# Power.net
KiCad netlist of a schematic drawn in Altium Designer
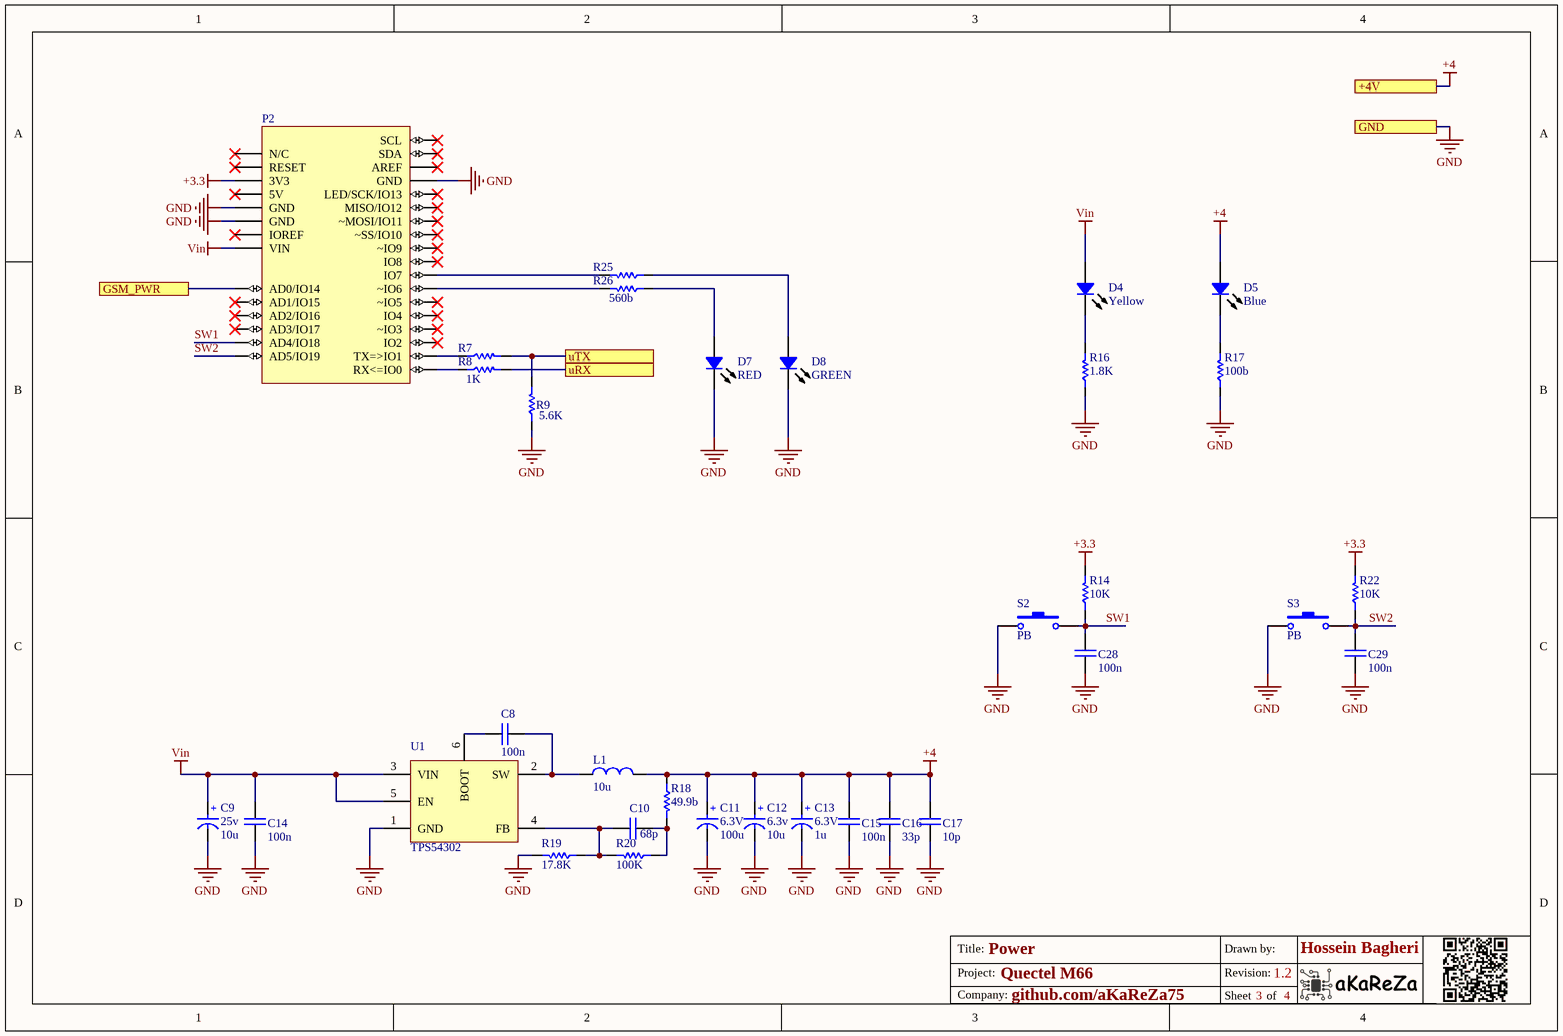
[diagram p0: Power.SchDoc]

(export (version "E")
  (design (tool "Eeschema 10.0.6"))
  (components
    (comp (ref "C8")
      (value "100n")
      (footprint "CAP 0805/2012")
      (description "Bipolar ceramic capacitor SMD")
      (fields (field (name "VALIDATION") "Valid"))
      (libsource (lib "aKaReZa") (part "Cap_Multi_SMD_100nF_0805"))
    )
    (comp (ref "C9")
      (value "10u")
      (footprint "SMT_C_Tantalum_B")
      (description "Tantalum Capacitor,TAJ Series-SMD")
      (fields (field (name "RATING") "25v") (field (name "VALIDATION") "Valid"))
      (libsource (lib "aKaReZa") (part "Cap_Tantalum"))
    )
    (comp (ref "C10")
      (value "68p")
      (footprint "CAP 0805/2012")
      (description "Bipolar ceramic capacitor SMD")
      (fields (field (name "VALIDATION") "Valid"))
      (libsource (lib "aKaReZa") (part "Cap_Multi_SMD_0805"))
    )
    (comp (ref "C11")
      (value "100u")
      (footprint "SMT_C_Tantalum_C")
      (description "Tantalum Capacitor,TAJ Series-SMD")
      (fields (field (name "RATING") "6.3V"))
      (libsource (lib "aKaReZa") (part "Cap_Tantalum"))
    )
    (comp (ref "C12")
      (value "10u")
      (footprint "SMT_C_Tantalum_A")
      (description "Tantalum Capacitor,TAJ Series-SMD")
      (fields (field (name "RATING") "6.3v") (field (name "VALIDATION") "Valid"))
      (libsource (lib "aKaReZa") (part "Cap_Tantalum"))
    )
    (comp (ref "C13")
      (value "1u")
      (footprint "SMT_C_Tantalum_A")
      (description "Tantalum Capacitor,TAJ Series-SMD")
      (fields (field (name "RATING") "6.3V"))
      (libsource (lib "aKaReZa") (part "Cap_Tantalum"))
    )
    (comp (ref "C14")
      (value "100n")
      (footprint "CAP 1206/3216")
      (description "Bipolar ceramic capacitor SMD")
      (fields (field (name "VALIDATION") "Valid"))
      (libsource (lib "aKaReZa") (part "Cap_Multi_SMD_100nF_1206"))
    )
    (comp (ref "C15")
      (value "100n")
      (footprint "CAP 1206/3216")
      (description "Bipolar ceramic capacitor SMD")
      (libsource (lib "aKaReZa") (part "Cap_Multi_SMD_100nF_1206"))
    )
    (comp (ref "C16")
      (value "33p")
      (footprint "CAP 1206/3216")
      (description "Bipolar ceramic capacitor SMD")
      (libsource (lib "aKaReZa") (part "Cap_Multi_SMD_1206"))
    )
    (comp (ref "C17")
      (value "10p")
      (footprint "CAP 1206/3216")
      (description "Bipolar ceramic capacitor SMD")
      (libsource (lib "aKaReZa") (part "Cap_Multi_SMD_1206"))
    )
    (comp (ref "C28")
      (value "100n")
      (footprint "CAP 0805/2012")
      (description "Bipolar ceramic capacitor SMD")
      (fields (field (name "VALIDATION") "Valid"))
      (libsource (lib "aKaReZa") (part "Cap_Multi_SMD_100nF_0805"))
    )
    (comp (ref "C29")
      (value "100n")
      (footprint "CAP 0805/2012")
      (description "Bipolar ceramic capacitor SMD")
      (fields (field (name "VALIDATION") "Valid"))
      (libsource (lib "aKaReZa") (part "Cap_Multi_SMD_100nF_0805"))
    )
    (comp (ref "D4")
      (value "Yellow")
      (footprint "LED 0805/2012 YELLOW")
      (description "LED")
      (fields (field (name "VALIDATION") "Valid"))
      (libsource (lib "aKaReZa") (part "Semi_LED_SMD"))
    )
    (comp (ref "D5")
      (value "Blue")
      (footprint "LED 0805/2012 BLUE")
      (description "LED")
      (fields (field (name "VALIDATION") "Valid"))
      (libsource (lib "aKaReZa") (part "Semi_LED_SMD"))
    )
    (comp (ref "D7")
      (value "RED")
      (footprint "LED 0805/2012 RED")
      (description "LED")
      (fields (field (name "VALIDATION") "Valid"))
      (libsource (lib "aKaReZa") (part "Semi_LED_SMD"))
    )
    (comp (ref "D8")
      (value "GREEN")
      (footprint "LED 0805/2012 GREEN")
      (description "LED")
      (fields (field (name "VALIDATION") "Valid"))
      (libsource (lib "aKaReZa") (part "Semi_LED_SMD"))
    )
    (comp (ref "L1")
      (value "10u")
      (footprint "L_7")
      (description "Inductor")
      (fields (field (name "VALIDATION") "Valid"))
      (libsource (lib "aKaReZa") (part "Ind_SMD"))
    )
    (comp (ref "P2")
      (value "UNO")
      (footprint "Arduino_uno_S_3")
      (description "Arduino uno slave")
      (fields (field (name "VALIDATION") "Valid"))
      (libsource (lib "aKaReZa") (part "Con_Arduino_UNO_S"))
    )
    (comp (ref "R7")
      (value "1K")
      (footprint "RES 0805 (2012X06L)")
      (description "Resistor")
      (fields (field (name "VALIDATION") "Valid"))
      (libsource (lib "aKaReZa") (part "Res_SMD_0805"))
    )
    (comp (ref "R8")
      (value "1K")
      (footprint "RES 0805 (2012X06L)")
      (description "Resistor")
      (fields (field (name "VALIDATION") "Valid"))
      (libsource (lib "aKaReZa") (part "Res_SMD_0805"))
    )
    (comp (ref "R9")
      (value "5.6K")
      (footprint "RES 0805 (2012X06L)")
      (description "Resistor")
      (fields (field (name "VALIDATION") "Valid"))
      (libsource (lib "aKaReZa") (part "Res_SMD_0805"))
    )
    (comp (ref "R14")
      (value "10K")
      (footprint "RES 0805 (2012X06L)")
      (description "Resistor")
      (fields (field (name "VALIDATION") "Valid"))
      (libsource (lib "aKaReZa") (part "Res_SMD_0805"))
    )
    (comp (ref "R16")
      (value "1.8K")
      (footprint "RES 0805 (2012X06L)")
      (description "Resistor")
      (fields (field (name "VALIDATION") "Valid"))
      (libsource (lib "aKaReZa") (part "Res_SMD_0805"))
    )
    (comp (ref "R17")
      (value "100b")
      (footprint "RES 0805 (2012X06L)")
      (description "Resistor")
      (fields (field (name "VALIDATION") "Valid"))
      (libsource (lib "aKaReZa") (part "Res_SMD_0805"))
    )
    (comp (ref "R18")
      (value "49.9b")
      (footprint "RES 0805 (2012X06L)")
      (description "Resistor")
      (fields (field (name "VALIDATION") "Valid"))
      (libsource (lib "aKaReZa") (part "Res_SMD_0805"))
    )
    (comp (ref "R19")
      (value "17.8K")
      (footprint "RES 0805 (2012X06L)")
      (description "Resistor")
      (fields (field (name "VALIDATION") "Valid"))
      (libsource (lib "aKaReZa") (part "Res_SMD_0805"))
    )
    (comp (ref "R20")
      (value "100K")
      (footprint "RES 0805 (2012X06L)")
      (description "Resistor")
      (fields (field (name "VALIDATION") "Valid"))
      (libsource (lib "aKaReZa") (part "Res_SMD_0805"))
    )
    (comp (ref "R22")
      (value "10K")
      (footprint "RES 0805 (2012X06L)")
      (description "Resistor")
      (fields (field (name "VALIDATION") "Valid"))
      (libsource (lib "aKaReZa") (part "Res_SMD_0805"))
    )
    (comp (ref "R25")
      (value "560b")
      (footprint "RES 0805 (2012X06L)")
      (description "Resistor")
      (fields (field (name "VALIDATION") "Valid"))
      (libsource (lib "aKaReZa") (part "Res_SMD_0805"))
    )
    (comp (ref "R26")
      (value "560b")
      (footprint "RES 0805 (2012X06L)")
      (description "Resistor")
      (fields (field (name "VALIDATION") "Valid"))
      (libsource (lib "aKaReZa") (part "Res_SMD_0805"))
    )
    (comp (ref "S2")
      (value "PB")
      (footprint "SW_PB_SMD_2PIN_SPST_6X3X2")
      (description "SMT Tactile ‎Switch")
      (fields (field (name "VALIDATION") "Valid"))
      (libsource (lib "aKaReZa") (part "SW_PushButton_2_SMD"))
    )
    (comp (ref "S3")
      (value "PB")
      (footprint "SW_PB_SMD_2PIN_SPST_6X3X2")
      (description "SMT Tactile ‎Switch")
      (fields (field (name "VALIDATION") "Valid"))
      (libsource (lib "aKaReZa") (part "SW_PushButton_2_SMD"))
    )
    (comp (ref "U1")
      (value "TPS54302")
      (footprint "TPS54302")
      (description "3'A Synchronous Step-Down Converter")
      (fields (field (name "VALIDATION") "Valid"))
      (libsource (lib "aKaReZa") (part "IC_Reg_TPS54302"))
    )
  )
  (nets
    (net (code "1") (name "+3.3") (class "Default")
      (node (ref "P2") (pin "4") (pinfunction "3V3_4") (pintype "power_in"))
      (node (ref "R14") (pin "2") (pinfunction "2_2") (pintype "passive"))
      (node (ref "R22") (pin "2") (pinfunction "2_2") (pintype "passive"))
    )
    (net (code "2") (name "+4") (class "Default")
      (node (ref "C11") (pin "1") (pinfunction "+_1") (pintype "passive"))
      (node (ref "C12") (pin "1") (pinfunction "+_1") (pintype "passive"))
      (node (ref "C13") (pin "1") (pinfunction "+_1") (pintype "passive"))
      (node (ref "C15") (pin "1") (pinfunction "1_1") (pintype "passive"))
      (node (ref "C16") (pin "1") (pinfunction "1_1") (pintype "passive"))
      (node (ref "C17") (pin "1") (pinfunction "1_1") (pintype "passive"))
      (node (ref "D5") (pin "1") (pinfunction "1_1") (pintype "passive"))
      (node (ref "L1") (pin "2") (pinfunction "2_2") (pintype "passive"))
      (node (ref "R18") (pin "1") (pinfunction "1_1") (pintype "passive"))
    )
    (net (code "3") (name "/GSM_PWR") (class "Default")
      (node (ref "P2") (pin "9") (pinfunction "AD0/IO14_9") (pintype "bidirectional"))
    )
    (net (code "4") (name "/SW1") (class "Default")
      (node (ref "C28") (pin "1") (pinfunction "1_1") (pintype "passive"))
      (node (ref "P2") (pin "13") (pinfunction "AD4/IO18_13") (pintype "bidirectional"))
      (node (ref "R14") (pin "1") (pinfunction "1_1") (pintype "passive"))
      (node (ref "S2") (pin "1") (pinfunction "1_1") (pintype "passive"))
    )
    (net (code "5") (name "/SW2") (class "Default")
      (node (ref "C29") (pin "1") (pinfunction "1_1") (pintype "passive"))
      (node (ref "P2") (pin "14") (pinfunction "AD5/IO19_14") (pintype "bidirectional"))
      (node (ref "R22") (pin "1") (pinfunction "1_1") (pintype "passive"))
      (node (ref "S3") (pin "1") (pinfunction "1_1") (pintype "passive"))
    )
    (net (code "6") (name "/uRX") (class "Default")
      (node (ref "R8") (pin "2") (pinfunction "2_2") (pintype "passive"))
    )
    (net (code "7") (name "/uTX") (class "Default")
      (node (ref "R7") (pin "2") (pinfunction "2_2") (pintype "passive"))
      (node (ref "R9") (pin "2") (pinfunction "2_2") (pintype "passive"))
    )
    (net (code "8") (name "GND") (class "Default")
      (node (ref "C11") (pin "2") (pinfunction "-_2") (pintype "passive"))
      (node (ref "C12") (pin "2") (pinfunction "-_2") (pintype "passive"))
      (node (ref "C13") (pin "2") (pinfunction "-_2") (pintype "passive"))
      (node (ref "C14") (pin "2") (pinfunction "2_2") (pintype "passive"))
      (node (ref "C15") (pin "2") (pinfunction "2_2") (pintype "passive"))
      (node (ref "C16") (pin "2") (pinfunction "2_2") (pintype "passive"))
      (node (ref "C17") (pin "2") (pinfunction "2_2") (pintype "passive"))
      (node (ref "C28") (pin "2") (pinfunction "2_2") (pintype "passive"))
      (node (ref "C29") (pin "2") (pinfunction "2_2") (pintype "passive"))
      (node (ref "C9") (pin "2") (pinfunction "-_2") (pintype "passive"))
      (node (ref "D7") (pin "2") (pinfunction "2_2") (pintype "passive"))
      (node (ref "D8") (pin "2") (pinfunction "2_2") (pintype "passive"))
      (node (ref "P2") (pin "29") (pinfunction "GND_29") (pintype "power_in"))
      (node (ref "P2") (pin "6") (pinfunction "GND_6") (pintype "power_in"))
      (node (ref "P2") (pin "7") (pinfunction "GND_7") (pintype "power_in"))
      (node (ref "R16") (pin "1") (pinfunction "1_1") (pintype "passive"))
      (node (ref "R17") (pin "1") (pinfunction "1_1") (pintype "passive"))
      (node (ref "R19") (pin "2") (pinfunction "2_2") (pintype "passive"))
      (node (ref "R9") (pin "1") (pinfunction "1_1") (pintype "passive"))
      (node (ref "S2") (pin "2") (pinfunction "2_2") (pintype "passive"))
      (node (ref "S3") (pin "2") (pinfunction "2_2") (pintype "passive"))
      (node (ref "U1") (pin "1") (pinfunction "GND_1") (pintype "power_in"))
    )
    (net (code "9") (name "Net-(C10-Pad2)") (class "Default")
      (node (ref "C10") (pin "2") (pinfunction "2_2") (pintype "passive"))
      (node (ref "R18") (pin "2") (pinfunction "2_2") (pintype "passive"))
      (node (ref "R20") (pin "1") (pinfunction "1_1") (pintype "passive"))
    )
    (net (code "10") (name "Net-(D4-Pad2)") (class "Default")
      (node (ref "D4") (pin "2") (pinfunction "2_2") (pintype "passive"))
      (node (ref "R16") (pin "2") (pinfunction "2_2") (pintype "passive"))
    )
    (net (code "11") (name "Net-(D5-Pad2)") (class "Default")
      (node (ref "D5") (pin "2") (pinfunction "2_2") (pintype "passive"))
      (node (ref "R17") (pin "2") (pinfunction "2_2") (pintype "passive"))
    )
    (net (code "12") (name "Net-(D7-Pad1)") (class "Default")
      (node (ref "D7") (pin "1") (pinfunction "1_1") (pintype "passive"))
      (node (ref "R26") (pin "1") (pinfunction "1_1") (pintype "passive"))
    )
    (net (code "13") (name "Net-(D8-Pad1)") (class "Default")
      (node (ref "D8") (pin "1") (pinfunction "1_1") (pintype "passive"))
      (node (ref "R25") (pin "1") (pinfunction "1_1") (pintype "passive"))
    )
    (net (code "14") (name "Net-(P2-IO7)") (class "Default")
      (node (ref "P2") (pin "22") (pinfunction "IO7_22") (pintype "bidirectional"))
      (node (ref "R25") (pin "2") (pinfunction "2_2") (pintype "passive"))
    )
    (net (code "15") (name "Net-(P2-RX<=IO0)") (class "Default")
      (node (ref "P2") (pin "15") (pinfunction "RX<=IO0_15") (pintype "bidirectional"))
      (node (ref "R8") (pin "1") (pinfunction "1_1") (pintype "passive"))
    )
    (net (code "16") (name "Net-(P2-TX=>IO1)") (class "Default")
      (node (ref "P2") (pin "16") (pinfunction "TX=>IO1_16") (pintype "bidirectional"))
      (node (ref "R7") (pin "1") (pinfunction "1_1") (pintype "passive"))
    )
    (net (code "17") (name "Net-(P2-~IO6)") (class "Default")
      (node (ref "P2") (pin "21") (pinfunction "~IO6_21") (pintype "bidirectional"))
      (node (ref "R26") (pin "2") (pinfunction "2_2") (pintype "passive"))
    )
    (net (code "18") (name "Net-(U1-BOOT)") (class "Default")
      (node (ref "C8") (pin "1") (pinfunction "1_1") (pintype "passive"))
      (node (ref "U1") (pin "6") (pinfunction "BOOT_6") (pintype "power_in"))
    )
    (net (code "19") (name "Net-(U1-FB)") (class "Default")
      (node (ref "C10") (pin "1") (pinfunction "1_1") (pintype "passive"))
      (node (ref "R19") (pin "1") (pinfunction "1_1") (pintype "passive"))
      (node (ref "R20") (pin "2") (pinfunction "2_2") (pintype "passive"))
      (node (ref "U1") (pin "4") (pinfunction "FB_4") (pintype "power_in"))
    )
    (net (code "20") (name "Net-(U1-SW)") (class "Default")
      (node (ref "C8") (pin "2") (pinfunction "2_2") (pintype "passive"))
      (node (ref "L1") (pin "1") (pinfunction "1_1") (pintype "passive"))
      (node (ref "U1") (pin "2") (pinfunction "SW_2") (pintype "power_in"))
    )
    (net (code "21") (name "Vin") (class "Default")
      (node (ref "C14") (pin "1") (pinfunction "1_1") (pintype "passive"))
      (node (ref "C9") (pin "1") (pinfunction "+_1") (pintype "passive"))
      (node (ref "D4") (pin "1") (pinfunction "1_1") (pintype "passive"))
      (node (ref "P2") (pin "8") (pinfunction "VIN_8") (pintype "power_in"))
      (node (ref "U1") (pin "3") (pinfunction "VIN_3") (pintype "power_in"))
      (node (ref "U1") (pin "5") (pinfunction "EN_5") (pintype "power_in"))
    )
    (net (code "22") (name "unconnected-(P2-5V-Pad5)") (class "Default")
      (node (ref "P2") (pin "5") (pinfunction "5V_5") (pintype "power_in+no_connect"))
    )
    (net (code "23") (name "unconnected-(P2-AD1{slash}IO15-Pad10)") (class "Default")
      (node (ref "P2") (pin "10") (pinfunction "AD1/IO15_10") (pintype "bidirectional+no_connect"))
    )
    (net (code "24") (name "unconnected-(P2-AD2{slash}IO16-Pad11)") (class "Default")
      (node (ref "P2") (pin "11") (pinfunction "AD2/IO16_11") (pintype "bidirectional+no_connect"))
    )
    (net (code "25") (name "unconnected-(P2-AD3{slash}IO17-Pad12)") (class "Default")
      (node (ref "P2") (pin "12") (pinfunction "AD3/IO17_12") (pintype "bidirectional+no_connect"))
    )
    (net (code "26") (name "unconnected-(P2-AREF-Pad30)") (class "Default")
      (node (ref "P2") (pin "30") (pinfunction "AREF_30") (pintype "passive+no_connect"))
    )
    (net (code "27") (name "unconnected-(P2-IO2-Pad17)") (class "Default")
      (node (ref "P2") (pin "17") (pinfunction "IO2_17") (pintype "bidirectional+no_connect"))
    )
    (net (code "28") (name "unconnected-(P2-IO4-Pad19)") (class "Default")
      (node (ref "P2") (pin "19") (pinfunction "IO4_19") (pintype "bidirectional+no_connect"))
    )
    (net (code "29") (name "unconnected-(P2-IO8-Pad23)") (class "Default")
      (node (ref "P2") (pin "23") (pinfunction "IO8_23") (pintype "bidirectional+no_connect"))
    )
    (net (code "30") (name "unconnected-(P2-IOREF-Pad2)") (class "Default")
      (node (ref "P2") (pin "2") (pinfunction "IOREF_2") (pintype "power_in+no_connect"))
    )
    (net (code "31") (name "unconnected-(P2-LED{slash}SCK{slash}IO13-Pad28)") (class "Default")
      (node (ref "P2") (pin "28") (pinfunction "LED/SCK/IO13_28") (pintype "bidirectional+no_connect"))
    )
    (net (code "32") (name "unconnected-(P2-MISO{slash}IO12-Pad27)") (class "Default")
      (node (ref "P2") (pin "27") (pinfunction "MISO/IO12_27") (pintype "bidirectional+no_connect"))
    )
    (net (code "33") (name "unconnected-(P2-N{slash}C-Pad1)") (class "Default")
      (node (ref "P2") (pin "1") (pinfunction "N/C_1") (pintype "passive+no_connect"))
    )
    (net (code "34") (name "unconnected-(P2-RESET-Pad3)") (class "Default")
      (node (ref "P2") (pin "3") (pinfunction "RESET_3") (pintype "passive+no_connect"))
    )
    (net (code "35") (name "unconnected-(P2-SCL-Pad32)") (class "Default")
      (node (ref "P2") (pin "32") (pinfunction "SCL_32") (pintype "bidirectional+no_connect"))
    )
    (net (code "36") (name "unconnected-(P2-SDA-Pad31)") (class "Default")
      (node (ref "P2") (pin "31") (pinfunction "SDA_31") (pintype "bidirectional+no_connect"))
    )
    (net (code "37") (name "unconnected-(P2-~IO3-Pad18)") (class "Default")
      (node (ref "P2") (pin "18") (pinfunction "~IO3_18") (pintype "bidirectional+no_connect"))
    )
    (net (code "38") (name "unconnected-(P2-~IO5-Pad20)") (class "Default")
      (node (ref "P2") (pin "20") (pinfunction "~IO5_20") (pintype "bidirectional+no_connect"))
    )
    (net (code "39") (name "unconnected-(P2-~IO9-Pad24)") (class "Default")
      (node (ref "P2") (pin "24") (pinfunction "~IO9_24") (pintype "bidirectional+no_connect"))
    )
    (net (code "40") (name "unconnected-(P2-~MOSI{slash}IO11-Pad26)") (class "Default")
      (node (ref "P2") (pin "26") (pinfunction "~MOSI/IO11_26") (pintype "bidirectional+no_connect"))
    )
    (net (code "41") (name "unconnected-(P2-~SS{slash}IO10-Pad25)") (class "Default")
      (node (ref "P2") (pin "25") (pinfunction "~SS/IO10_25") (pintype "bidirectional+no_connect"))
    )
  )
)
